# Schematic.net
KiCad netlist of a schematic drawn in Altium Designer
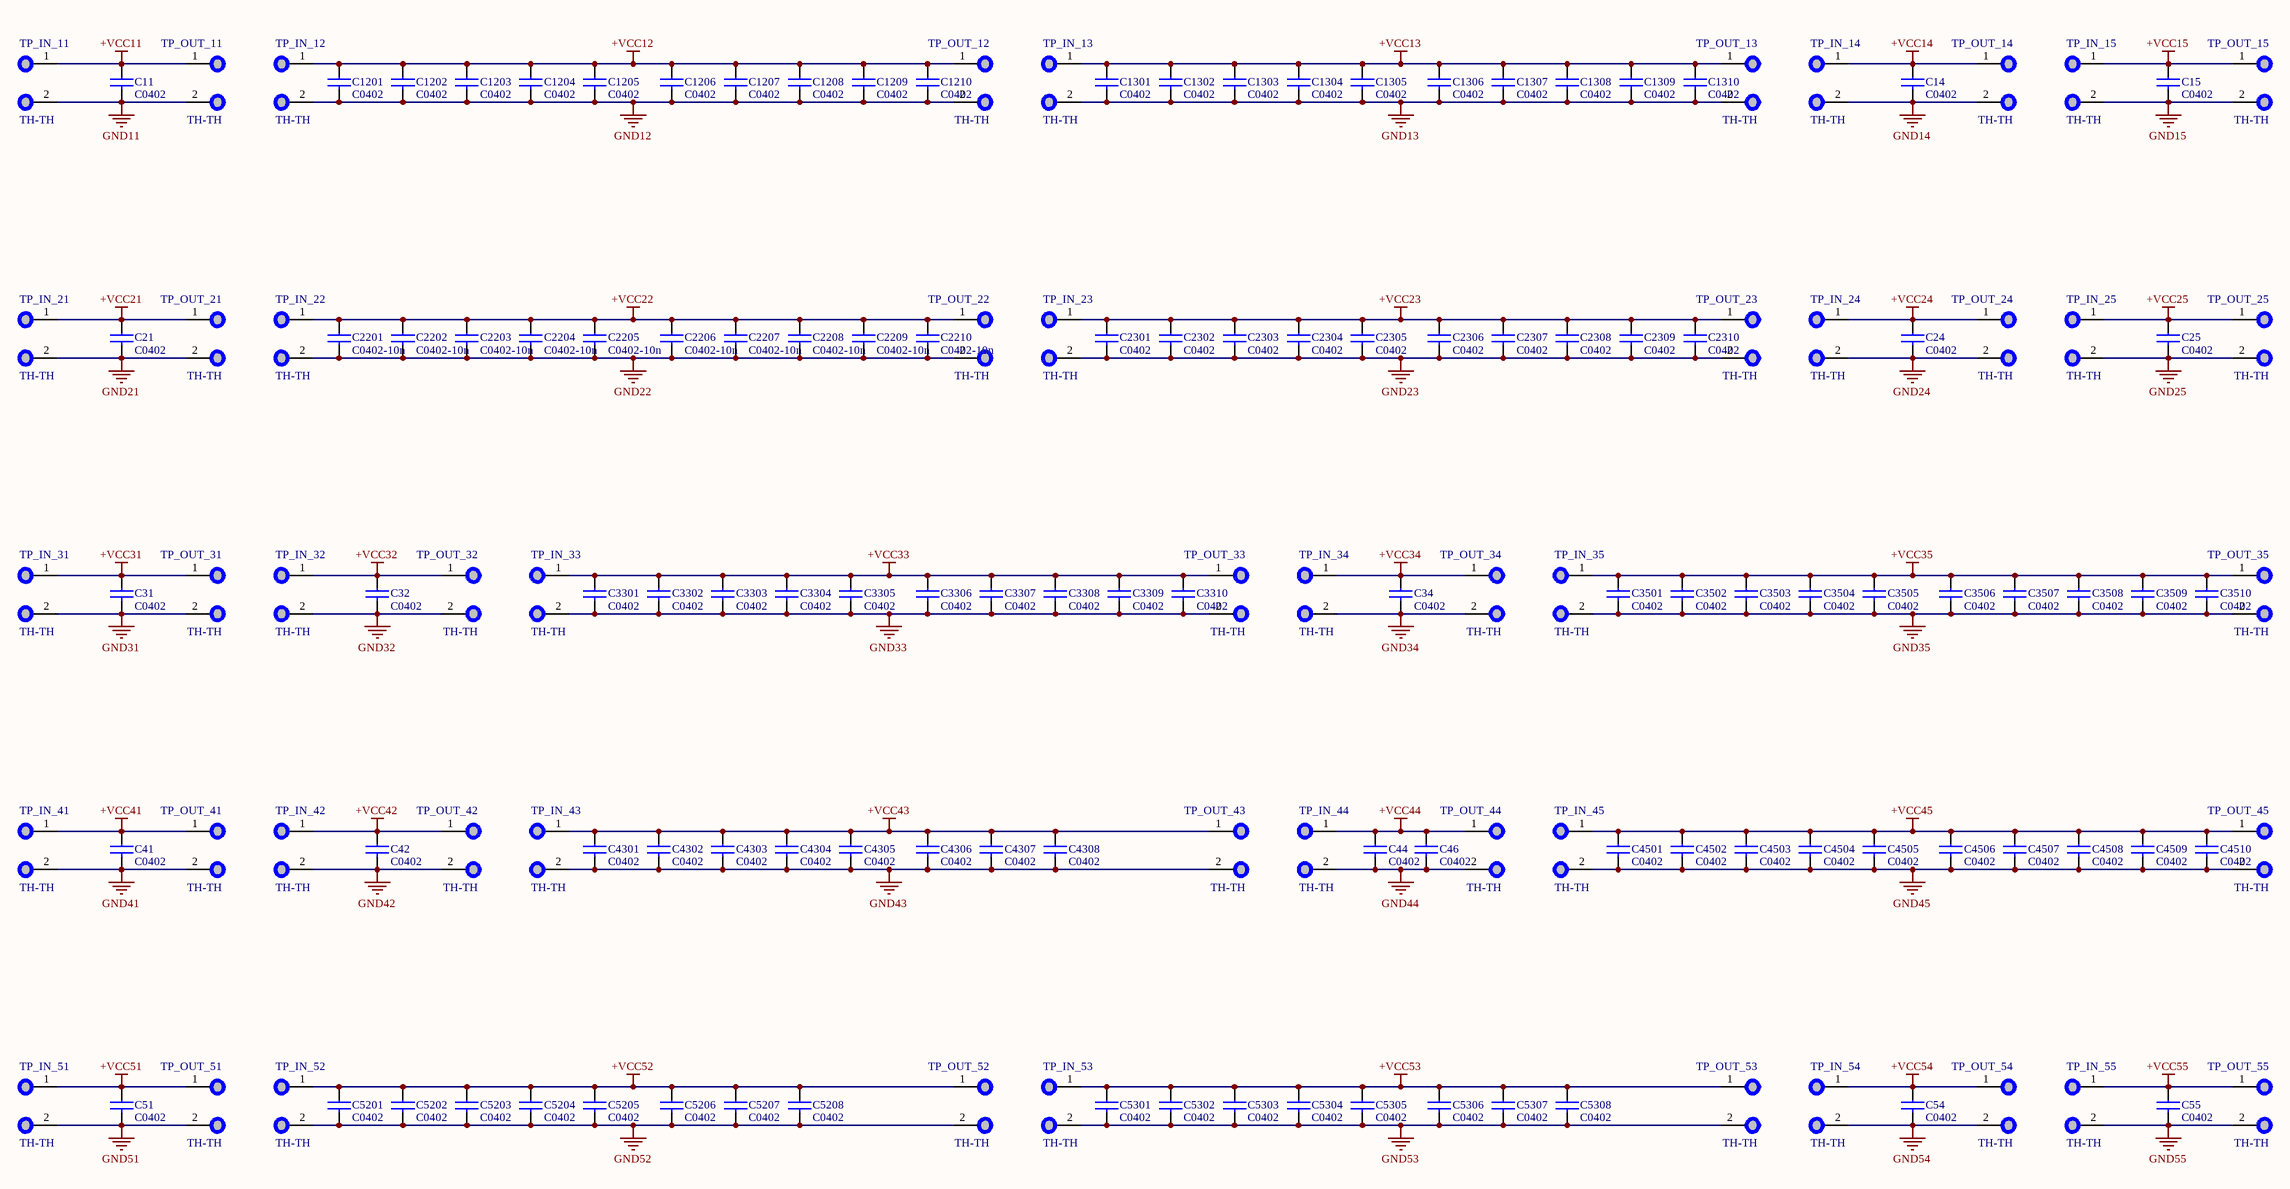
[diagram p0: Schematic.SchDoc]

(export (version "E")
  (design (tool "Eeschema 10.0.6"))
  (components
    (comp (ref "C11") (value "C0402") (footprint "C0402") (libsource (lib "Schlib") (part "CAP0402")))
    (comp (ref "C14") (value "C0402") (footprint "C0402") (libsource (lib "Schlib") (part "CAP0402")))
    (comp (ref "C15") (value "C0402") (footprint "C0402") (libsource (lib "Schlib") (part "CAP0402")))
    (comp (ref "C21") (value "C0402") (footprint "C0402") (libsource (lib "Schlib") (part "CAP0402")))
    (comp (ref "C24") (value "C0402") (footprint "C0402") (libsource (lib "Schlib") (part "CAP0402")))
    (comp (ref "C25") (value "C0402") (footprint "C0402") (libsource (lib "Schlib") (part "CAP0402")))
    (comp (ref "C31") (value "C0402") (footprint "C0402") (libsource (lib "Schlib") (part "CAP0402")))
    (comp (ref "C32") (value "C0402") (footprint "C0402") (libsource (lib "Schlib") (part "CAP0402")))
    (comp (ref "C34") (value "C0402") (footprint "C0402") (libsource (lib "Schlib") (part "CAP0402")))
    (comp (ref "C41") (value "C0402") (footprint "C0402") (libsource (lib "Schlib") (part "CAP0402")))
    (comp (ref "C42") (value "C0402") (footprint "C0402") (libsource (lib "Schlib") (part "CAP0402")))
    (comp (ref "C44") (value "C0402") (footprint "C0402") (libsource (lib "Schlib") (part "CAP0402")))
    (comp (ref "C46") (value "C0402") (footprint "C0402") (libsource (lib "Schlib") (part "CAP0402")))
    (comp (ref "C51") (value "C0402") (footprint "C0402") (libsource (lib "Schlib") (part "CAP0402")))
    (comp (ref "C54") (value "C0402") (footprint "C0402") (libsource (lib "Schlib") (part "CAP0402")))
    (comp (ref "C55") (value "C0402") (footprint "C0402") (libsource (lib "Schlib") (part "CAP0402")))
    (comp (ref "C1201") (value "C0402") (footprint "C0402") (libsource (lib "Schlib") (part "CAP0402")))
    (comp (ref "C1202") (value "C0402") (footprint "C0402") (libsource (lib "Schlib") (part "CAP0402")))
    (comp (ref "C1203") (value "C0402") (footprint "C0402") (libsource (lib "Schlib") (part "CAP0402")))
    (comp (ref "C1204") (value "C0402") (footprint "C0402") (libsource (lib "Schlib") (part "CAP0402")))
    (comp (ref "C1205") (value "C0402") (footprint "C0402") (libsource (lib "Schlib") (part "CAP0402")))
    (comp (ref "C1206") (value "C0402") (footprint "C0402") (libsource (lib "Schlib") (part "CAP0402")))
    (comp (ref "C1207") (value "C0402") (footprint "C0402") (libsource (lib "Schlib") (part "CAP0402")))
    (comp (ref "C1208") (value "C0402") (footprint "C0402") (libsource (lib "Schlib") (part "CAP0402")))
    (comp (ref "C1209") (value "C0402") (footprint "C0402") (libsource (lib "Schlib") (part "CAP0402")))
    (comp (ref "C1210") (value "C0402") (footprint "C0402") (libsource (lib "Schlib") (part "CAP0402")))
    (comp (ref "C1301") (value "C0402") (footprint "C0402") (libsource (lib "Schlib") (part "CAP0402")))
    (comp (ref "C1302") (value "C0402") (footprint "C0402") (libsource (lib "Schlib") (part "CAP0402")))
    (comp (ref "C1303") (value "C0402") (footprint "C0402") (libsource (lib "Schlib") (part "CAP0402")))
    (comp (ref "C1304") (value "C0402") (footprint "C0402") (libsource (lib "Schlib") (part "CAP0402")))
    (comp (ref "C1305") (value "C0402") (footprint "C0402") (libsource (lib "Schlib") (part "CAP0402")))
    (comp (ref "C1306") (value "C0402") (footprint "C0402") (libsource (lib "Schlib") (part "CAP0402")))
    (comp (ref "C1307") (value "C0402") (footprint "C0402") (libsource (lib "Schlib") (part "CAP0402")))
    (comp (ref "C1308") (value "C0402") (footprint "C0402") (libsource (lib "Schlib") (part "CAP0402")))
    (comp (ref "C1309") (value "C0402") (footprint "C0402") (libsource (lib "Schlib") (part "CAP0402")))
    (comp (ref "C1310") (value "C0402") (footprint "C0402") (libsource (lib "Schlib") (part "CAP0402")))
    (comp (ref "C2201") (value "C0402-10n") (footprint "C0402") (libsource (lib "Schlib") (part "CAP0402")))
    (comp (ref "C2202") (value "C0402-10n") (footprint "C0402") (libsource (lib "Schlib") (part "CAP0402")))
    (comp (ref "C2203") (value "C0402-10n") (footprint "C0402") (libsource (lib "Schlib") (part "CAP0402")))
    (comp (ref "C2204") (value "C0402-10n") (footprint "C0402") (libsource (lib "Schlib") (part "CAP0402")))
    (comp (ref "C2205") (value "C0402-10n") (footprint "C0402") (libsource (lib "Schlib") (part "CAP0402")))
    (comp (ref "C2206") (value "C0402-10n") (footprint "C0402") (libsource (lib "Schlib") (part "CAP0402")))
    (comp (ref "C2207") (value "C0402-10n") (footprint "C0402") (libsource (lib "Schlib") (part "CAP0402")))
    (comp (ref "C2208") (value "C0402-10n") (footprint "C0402") (libsource (lib "Schlib") (part "CAP0402")))
    (comp (ref "C2209") (value "C0402-10n") (footprint "C0402") (libsource (lib "Schlib") (part "CAP0402")))
    (comp (ref "C2210") (value "C0402-10n") (footprint "C0402") (libsource (lib "Schlib") (part "CAP0402")))
    (comp (ref "C2301") (value "C0402") (footprint "C0402") (libsource (lib "Schlib") (part "CAP0402")))
    (comp (ref "C2302") (value "C0402") (footprint "C0402") (libsource (lib "Schlib") (part "CAP0402")))
    (comp (ref "C2303") (value "C0402") (footprint "C0402") (libsource (lib "Schlib") (part "CAP0402")))
    (comp (ref "C2304") (value "C0402") (footprint "C0402") (libsource (lib "Schlib") (part "CAP0402")))
    (comp (ref "C2305") (value "C0402") (footprint "C0402") (libsource (lib "Schlib") (part "CAP0402")))
    (comp (ref "C2306") (value "C0402") (footprint "C0402") (libsource (lib "Schlib") (part "CAP0402")))
    (comp (ref "C2307") (value "C0402") (footprint "C0402") (libsource (lib "Schlib") (part "CAP0402")))
    (comp (ref "C2308") (value "C0402") (footprint "C0402") (libsource (lib "Schlib") (part "CAP0402")))
    (comp (ref "C2309") (value "C0402") (footprint "C0402") (libsource (lib "Schlib") (part "CAP0402")))
    (comp (ref "C2310") (value "C0402") (footprint "C0402") (libsource (lib "Schlib") (part "CAP0402")))
    (comp (ref "C3301") (value "C0402") (footprint "C0402") (libsource (lib "Schlib") (part "CAP0402")))
    (comp (ref "C3302") (value "C0402") (footprint "C0402") (libsource (lib "Schlib") (part "CAP0402")))
    (comp (ref "C3303") (value "C0402") (footprint "C0402") (libsource (lib "Schlib") (part "CAP0402")))
    (comp (ref "C3304") (value "C0402") (footprint "C0402") (libsource (lib "Schlib") (part "CAP0402")))
    (comp (ref "C3305") (value "C0402") (footprint "C0402") (libsource (lib "Schlib") (part "CAP0402")))
    (comp (ref "C3306") (value "C0402") (footprint "C0402") (libsource (lib "Schlib") (part "CAP0402")))
    (comp (ref "C3307") (value "C0402") (footprint "C0402") (libsource (lib "Schlib") (part "CAP0402")))
    (comp (ref "C3308") (value "C0402") (footprint "C0402") (libsource (lib "Schlib") (part "CAP0402")))
    (comp (ref "C3309") (value "C0402") (footprint "C0402") (libsource (lib "Schlib") (part "CAP0402")))
    (comp (ref "C3310") (value "C0402") (footprint "C0402") (libsource (lib "Schlib") (part "CAP0402")))
    (comp (ref "C3501") (value "C0402") (footprint "C0402") (libsource (lib "Schlib") (part "CAP0402")))
    (comp (ref "C3502") (value "C0402") (footprint "C0402") (libsource (lib "Schlib") (part "CAP0402")))
    (comp (ref "C3503") (value "C0402") (footprint "C0402") (libsource (lib "Schlib") (part "CAP0402")))
    (comp (ref "C3504") (value "C0402") (footprint "C0402") (libsource (lib "Schlib") (part "CAP0402")))
    (comp (ref "C3505") (value "C0402") (footprint "C0402") (libsource (lib "Schlib") (part "CAP0402")))
    (comp (ref "C3506") (value "C0402") (footprint "C0402") (libsource (lib "Schlib") (part "CAP0402")))
    (comp (ref "C3507") (value "C0402") (footprint "C0402") (libsource (lib "Schlib") (part "CAP0402")))
    (comp (ref "C3508") (value "C0402") (footprint "C0402") (libsource (lib "Schlib") (part "CAP0402")))
    (comp (ref "C3509") (value "C0402") (footprint "C0402") (libsource (lib "Schlib") (part "CAP0402")))
    (comp (ref "C3510") (value "C0402") (footprint "C0402") (libsource (lib "Schlib") (part "CAP0402")))
    (comp (ref "C4301") (value "C0402") (footprint "C0402") (libsource (lib "Schlib") (part "CAP0402")))
    (comp (ref "C4302") (value "C0402") (footprint "C0402") (libsource (lib "Schlib") (part "CAP0402")))
    (comp (ref "C4303") (value "C0402") (footprint "C0402") (libsource (lib "Schlib") (part "CAP0402")))
    (comp (ref "C4304") (value "C0402") (footprint "C0402") (libsource (lib "Schlib") (part "CAP0402")))
    (comp (ref "C4305") (value "C0402") (footprint "C0402") (libsource (lib "Schlib") (part "CAP0402")))
    (comp (ref "C4306") (value "C0402") (footprint "C0402") (libsource (lib "Schlib") (part "CAP0402")))
    (comp (ref "C4307") (value "C0402") (footprint "C0402") (libsource (lib "Schlib") (part "CAP0402")))
    (comp (ref "C4308") (value "C0402") (footprint "C0402") (libsource (lib "Schlib") (part "CAP0402")))
    (comp (ref "C4501") (value "C0402") (footprint "C0402") (libsource (lib "Schlib") (part "CAP0402")))
    (comp (ref "C4502") (value "C0402") (footprint "C0402") (libsource (lib "Schlib") (part "CAP0402")))
    (comp (ref "C4503") (value "C0402") (footprint "C0402") (libsource (lib "Schlib") (part "CAP0402")))
    (comp (ref "C4504") (value "C0402") (footprint "C0402") (libsource (lib "Schlib") (part "CAP0402")))
    (comp (ref "C4505") (value "C0402") (footprint "C0402") (libsource (lib "Schlib") (part "CAP0402")))
    (comp (ref "C4506") (value "C0402") (footprint "C0402") (libsource (lib "Schlib") (part "CAP0402")))
    (comp (ref "C4507") (value "C0402") (footprint "C0402") (libsource (lib "Schlib") (part "CAP0402")))
    (comp (ref "C4508") (value "C0402") (footprint "C0402") (libsource (lib "Schlib") (part "CAP0402")))
    (comp (ref "C4509") (value "C0402") (footprint "C0402") (libsource (lib "Schlib") (part "CAP0402")))
    (comp (ref "C4510") (value "C0402") (footprint "C0402") (libsource (lib "Schlib") (part "CAP0402")))
    (comp (ref "C5201") (value "C0402") (footprint "C0402") (libsource (lib "Schlib") (part "CAP0402")))
    (comp (ref "C5202") (value "C0402") (footprint "C0402") (libsource (lib "Schlib") (part "CAP0402")))
    (comp (ref "C5203") (value "C0402") (footprint "C0402") (libsource (lib "Schlib") (part "CAP0402")))
    (comp (ref "C5204") (value "C0402") (footprint "C0402") (libsource (lib "Schlib") (part "CAP0402")))
    (comp (ref "C5205") (value "C0402") (footprint "C0402") (libsource (lib "Schlib") (part "CAP0402")))
    (comp (ref "C5206") (value "C0402") (footprint "C0402") (libsource (lib "Schlib") (part "CAP0402")))
    (comp (ref "C5207") (value "C0402") (footprint "C0402") (libsource (lib "Schlib") (part "CAP0402")))
    (comp (ref "C5208") (value "C0402") (footprint "C0402") (libsource (lib "Schlib") (part "CAP0402")))
    (comp (ref "C5301") (value "C0402") (footprint "C0402") (libsource (lib "Schlib") (part "CAP0402")))
    (comp (ref "C5302") (value "C0402") (footprint "C0402") (libsource (lib "Schlib") (part "CAP0402")))
    (comp (ref "C5303") (value "C0402") (footprint "C0402") (libsource (lib "Schlib") (part "CAP0402")))
    (comp (ref "C5304") (value "C0402") (footprint "C0402") (libsource (lib "Schlib") (part "CAP0402")))
    (comp (ref "C5305") (value "C0402") (footprint "C0402") (libsource (lib "Schlib") (part "CAP0402")))
    (comp (ref "C5306") (value "C0402") (footprint "C0402") (libsource (lib "Schlib") (part "CAP0402")))
    (comp (ref "C5307") (value "C0402") (footprint "C0402") (libsource (lib "Schlib") (part "CAP0402")))
    (comp (ref "C5308") (value "C0402") (footprint "C0402") (libsource (lib "Schlib") (part "CAP0402")))
    (comp (ref "TP_IN_11")
      (value "TH-TH")
      (footprint "TP_TH_TH")
      (description "Testpoints TH - TH 1mm/0.3mm")
      (libsource (lib "Schlib") (part "TP_TH_TH"))
    )
    (comp (ref "TP_IN_12")
      (value "TH-TH")
      (footprint "TP_TH_TH")
      (description "Testpoints TH - TH 1mm/0.3mm")
      (libsource (lib "Schlib") (part "TP_TH_TH"))
    )
    (comp (ref "TP_IN_13")
      (value "TH-TH")
      (footprint "TP_TH_TH")
      (description "Testpoints TH - TH 1mm/0.3mm")
      (libsource (lib "Schlib") (part "TP_TH_TH"))
    )
    (comp (ref "TP_IN_14")
      (value "TH-TH")
      (footprint "TP_TH_TH")
      (description "Testpoints TH - TH 1mm/0.3mm")
      (libsource (lib "Schlib") (part "TP_TH_TH"))
    )
    (comp (ref "TP_IN_15")
      (value "TH-TH")
      (footprint "TP_TH_TH")
      (description "Testpoints TH - TH 1mm/0.3mm")
      (libsource (lib "Schlib") (part "TP_TH_TH"))
    )
    (comp (ref "TP_IN_21")
      (value "TH-TH")
      (footprint "TP_TH_TH")
      (description "Testpoints TH - TH 1mm/0.3mm")
      (libsource (lib "Schlib") (part "TP_TH_TH"))
    )
    (comp (ref "TP_IN_22")
      (value "TH-TH")
      (footprint "TP_TH_TH")
      (description "Testpoints TH - TH 1mm/0.3mm")
      (libsource (lib "Schlib") (part "TP_TH_TH"))
    )
    (comp (ref "TP_IN_23")
      (value "TH-TH")
      (footprint "TP_TH_TH")
      (description "Testpoints TH - TH 1mm/0.3mm")
      (libsource (lib "Schlib") (part "TP_TH_TH"))
    )
    (comp (ref "TP_IN_24")
      (value "TH-TH")
      (footprint "TP_TH_TH")
      (description "Testpoints TH - TH 1mm/0.3mm")
      (libsource (lib "Schlib") (part "TP_TH_TH"))
    )
    (comp (ref "TP_IN_25")
      (value "TH-TH")
      (footprint "TP_TH_TH")
      (description "Testpoints TH - TH 1mm/0.3mm")
      (libsource (lib "Schlib") (part "TP_TH_TH"))
    )
    (comp (ref "TP_IN_31")
      (value "TH-TH")
      (footprint "TP_TH_TH")
      (description "Testpoints TH - TH 1mm/0.3mm")
      (libsource (lib "Schlib") (part "TP_TH_TH"))
    )
    (comp (ref "TP_IN_32")
      (value "TH-TH")
      (footprint "TP_TH_TH")
      (description "Testpoints TH - TH 1mm/0.3mm")
      (libsource (lib "Schlib") (part "TP_TH_TH"))
    )
    (comp (ref "TP_IN_33")
      (value "TH-TH")
      (footprint "TP_TH_TH")
      (description "Testpoints TH - TH 1mm/0.3mm")
      (libsource (lib "Schlib") (part "TP_TH_TH"))
    )
    (comp (ref "TP_IN_34")
      (value "TH-TH")
      (footprint "TP_TH_TH")
      (description "Testpoints TH - TH 1mm/0.3mm")
      (libsource (lib "Schlib") (part "TP_TH_TH"))
    )
    (comp (ref "TP_IN_35")
      (value "TH-TH")
      (footprint "TP_TH_TH")
      (description "Testpoints TH - TH 1mm/0.3mm")
      (libsource (lib "Schlib") (part "TP_TH_TH"))
    )
    (comp (ref "TP_IN_41")
      (value "TH-TH")
      (footprint "TP_TH_TH")
      (description "Testpoints TH - TH 1mm/0.3mm")
      (libsource (lib "Schlib") (part "TP_TH_TH"))
    )
    (comp (ref "TP_IN_42")
      (value "TH-TH")
      (footprint "TP_TH_TH")
      (description "Testpoints TH - TH 1mm/0.3mm")
      (libsource (lib "Schlib") (part "TP_TH_TH"))
    )
    (comp (ref "TP_IN_43")
      (value "TH-TH")
      (footprint "TP_TH_TH")
      (description "Testpoints TH - TH 1mm/0.3mm")
      (libsource (lib "Schlib") (part "TP_TH_TH"))
    )
    (comp (ref "TP_IN_44")
      (value "TH-TH")
      (footprint "TP_TH_TH")
      (description "Testpoints TH - TH 1mm/0.3mm")
      (libsource (lib "Schlib") (part "TP_TH_TH"))
    )
    (comp (ref "TP_IN_45")
      (value "TH-TH")
      (footprint "TP_TH_TH")
      (description "Testpoints TH - TH 1mm/0.3mm")
      (libsource (lib "Schlib") (part "TP_TH_TH"))
    )
    (comp (ref "TP_IN_51")
      (value "TH-TH")
      (footprint "TP_TH_TH")
      (description "Testpoints TH - TH 1mm/0.3mm")
      (libsource (lib "Schlib") (part "TP_TH_TH"))
    )
    (comp (ref "TP_IN_52")
      (value "TH-TH")
      (footprint "TP_TH_TH")
      (description "Testpoints TH - TH 1mm/0.3mm")
      (libsource (lib "Schlib") (part "TP_TH_TH"))
    )
    (comp (ref "TP_IN_53")
      (value "TH-TH")
      (footprint "TP_TH_TH")
      (description "Testpoints TH - TH 1mm/0.3mm")
      (libsource (lib "Schlib") (part "TP_TH_TH"))
    )
    (comp (ref "TP_IN_54")
      (value "TH-TH")
      (footprint "TP_TH_TH")
      (description "Testpoints TH - TH 1mm/0.3mm")
      (libsource (lib "Schlib") (part "TP_TH_TH"))
    )
    (comp (ref "TP_IN_55")
      (value "TH-TH")
      (footprint "TP_TH_TH")
      (description "Testpoints TH - TH 1mm/0.3mm")
      (libsource (lib "Schlib") (part "TP_TH_TH"))
    )
    (comp (ref "TP_OUT_11")
      (value "TH-TH")
      (footprint "TP_TH_TH")
      (description "Testpoints TH - TH 1mm/0.3mm")
      (libsource (lib "Schlib") (part "TP_TH_TH"))
    )
    (comp (ref "TP_OUT_12")
      (value "TH-TH")
      (footprint "TP_TH_TH")
      (description "Testpoints TH - TH 1mm/0.3mm")
      (libsource (lib "Schlib") (part "TP_TH_TH"))
    )
    (comp (ref "TP_OUT_13")
      (value "TH-TH")
      (footprint "TP_TH_TH")
      (description "Testpoints TH - TH 1mm/0.3mm")
      (libsource (lib "Schlib") (part "TP_TH_TH"))
    )
    (comp (ref "TP_OUT_14")
      (value "TH-TH")
      (footprint "TP_TH_TH")
      (description "Testpoints TH - TH 1mm/0.3mm")
      (libsource (lib "Schlib") (part "TP_TH_TH"))
    )
    (comp (ref "TP_OUT_15")
      (value "TH-TH")
      (footprint "TP_TH_TH")
      (description "Testpoints TH - TH 1mm/0.3mm")
      (libsource (lib "Schlib") (part "TP_TH_TH"))
    )
    (comp (ref "TP_OUT_21")
      (value "TH-TH")
      (footprint "TP_TH_TH")
      (description "Testpoints TH - TH 1mm/0.3mm")
      (libsource (lib "Schlib") (part "TP_TH_TH"))
    )
    (comp (ref "TP_OUT_22")
      (value "TH-TH")
      (footprint "TP_TH_TH")
      (description "Testpoints TH - TH 1mm/0.3mm")
      (libsource (lib "Schlib") (part "TP_TH_TH"))
    )
    (comp (ref "TP_OUT_23")
      (value "TH-TH")
      (footprint "TP_TH_TH")
      (description "Testpoints TH - TH 1mm/0.3mm")
      (libsource (lib "Schlib") (part "TP_TH_TH"))
    )
    (comp (ref "TP_OUT_24")
      (value "TH-TH")
      (footprint "TP_TH_TH")
      (description "Testpoints TH - TH 1mm/0.3mm")
      (libsource (lib "Schlib") (part "TP_TH_TH"))
    )
    (comp (ref "TP_OUT_25")
      (value "TH-TH")
      (footprint "TP_TH_TH")
      (description "Testpoints TH - TH 1mm/0.3mm")
      (libsource (lib "Schlib") (part "TP_TH_TH"))
    )
    (comp (ref "TP_OUT_31")
      (value "TH-TH")
      (footprint "TP_TH_TH")
      (description "Testpoints TH - TH 1mm/0.3mm")
      (libsource (lib "Schlib") (part "TP_TH_TH"))
    )
    (comp (ref "TP_OUT_32")
      (value "TH-TH")
      (footprint "TP_TH_TH")
      (description "Testpoints TH - TH 1mm/0.3mm")
      (libsource (lib "Schlib") (part "TP_TH_TH"))
    )
    (comp (ref "TP_OUT_33")
      (value "TH-TH")
      (footprint "TP_TH_TH")
      (description "Testpoints TH - TH 1mm/0.3mm")
      (libsource (lib "Schlib") (part "TP_TH_TH"))
    )
    (comp (ref "TP_OUT_34")
      (value "TH-TH")
      (footprint "TP_TH_TH")
      (description "Testpoints TH - TH 1mm/0.3mm")
      (libsource (lib "Schlib") (part "TP_TH_TH"))
    )
    (comp (ref "TP_OUT_35")
      (value "TH-TH")
      (footprint "TP_TH_TH")
      (description "Testpoints TH - TH 1mm/0.3mm")
      (libsource (lib "Schlib") (part "TP_TH_TH"))
    )
    (comp (ref "TP_OUT_41")
      (value "TH-TH")
      (footprint "TP_TH_TH")
      (description "Testpoints TH - TH 1mm/0.3mm")
      (libsource (lib "Schlib") (part "TP_TH_TH"))
    )
    (comp (ref "TP_OUT_42")
      (value "TH-TH")
      (footprint "TP_TH_TH")
      (description "Testpoints TH - TH 1mm/0.3mm")
      (libsource (lib "Schlib") (part "TP_TH_TH"))
    )
    (comp (ref "TP_OUT_43")
      (value "TH-TH")
      (footprint "TP_TH_TH")
      (description "Testpoints TH - TH 1mm/0.3mm")
      (libsource (lib "Schlib") (part "TP_TH_TH"))
    )
    (comp (ref "TP_OUT_44")
      (value "TH-TH")
      (footprint "TP_TH_TH")
      (description "Testpoints TH - TH 1mm/0.3mm")
      (libsource (lib "Schlib") (part "TP_TH_TH"))
    )
    (comp (ref "TP_OUT_45")
      (value "TH-TH")
      (footprint "TP_TH_TH")
      (description "Testpoints TH - TH 1mm/0.3mm")
      (libsource (lib "Schlib") (part "TP_TH_TH"))
    )
    (comp (ref "TP_OUT_51")
      (value "TH-TH")
      (footprint "TP_TH_TH")
      (description "Testpoints TH - TH 1mm/0.3mm")
      (libsource (lib "Schlib") (part "TP_TH_TH"))
    )
    (comp (ref "TP_OUT_52")
      (value "TH-TH")
      (footprint "TP_TH_TH")
      (description "Testpoints TH - TH 1mm/0.3mm")
      (libsource (lib "Schlib") (part "TP_TH_TH"))
    )
    (comp (ref "TP_OUT_53")
      (value "TH-TH")
      (footprint "TP_TH_TH")
      (description "Testpoints TH - TH 1mm/0.3mm")
      (libsource (lib "Schlib") (part "TP_TH_TH"))
    )
    (comp (ref "TP_OUT_54")
      (value "TH-TH")
      (footprint "TP_TH_TH")
      (description "Testpoints TH - TH 1mm/0.3mm")
      (libsource (lib "Schlib") (part "TP_TH_TH"))
    )
    (comp (ref "TP_OUT_55")
      (value "TH-TH")
      (footprint "TP_TH_TH")
      (description "Testpoints TH - TH 1mm/0.3mm")
      (libsource (lib "Schlib") (part "TP_TH_TH"))
    )
  )
  (nets
    (net (code "1") (name "+VCC11") (class "Default")
      (node (ref "C11") (pin "1") (pinfunction "1_1") (pintype "passive"))
      (node (ref "TP_IN_11") (pin "1") (pinfunction "1_1") (pintype "passive"))
      (node (ref "TP_OUT_11") (pin "1") (pinfunction "1_1") (pintype "passive"))
    )
    (net (code "2") (name "+VCC12") (class "Default")
      (node (ref "C1201") (pin "1") (pinfunction "1_1") (pintype "passive"))
      (node (ref "C1202") (pin "1") (pinfunction "1_1") (pintype "passive"))
      (node (ref "C1203") (pin "1") (pinfunction "1_1") (pintype "passive"))
      (node (ref "C1204") (pin "1") (pinfunction "1_1") (pintype "passive"))
      (node (ref "C1205") (pin "1") (pinfunction "1_1") (pintype "passive"))
      (node (ref "C1206") (pin "1") (pinfunction "1_1") (pintype "passive"))
      (node (ref "C1207") (pin "1") (pinfunction "1_1") (pintype "passive"))
      (node (ref "C1208") (pin "1") (pinfunction "1_1") (pintype "passive"))
      (node (ref "C1209") (pin "1") (pinfunction "1_1") (pintype "passive"))
      (node (ref "C1210") (pin "1") (pinfunction "1_1") (pintype "passive"))
      (node (ref "TP_IN_12") (pin "1") (pinfunction "1_1") (pintype "passive"))
      (node (ref "TP_OUT_12") (pin "1") (pinfunction "1_1") (pintype "passive"))
    )
    (net (code "3") (name "+VCC13") (class "Default")
      (node (ref "C1301") (pin "1") (pinfunction "1_1") (pintype "passive"))
      (node (ref "C1302") (pin "1") (pinfunction "1_1") (pintype "passive"))
      (node (ref "C1303") (pin "1") (pinfunction "1_1") (pintype "passive"))
      (node (ref "C1304") (pin "1") (pinfunction "1_1") (pintype "passive"))
      (node (ref "C1305") (pin "1") (pinfunction "1_1") (pintype "passive"))
      (node (ref "C1306") (pin "1") (pinfunction "1_1") (pintype "passive"))
      (node (ref "C1307") (pin "1") (pinfunction "1_1") (pintype "passive"))
      (node (ref "C1308") (pin "1") (pinfunction "1_1") (pintype "passive"))
      (node (ref "C1309") (pin "1") (pinfunction "1_1") (pintype "passive"))
      (node (ref "C1310") (pin "1") (pinfunction "1_1") (pintype "passive"))
      (node (ref "TP_IN_13") (pin "1") (pinfunction "1_1") (pintype "passive"))
      (node (ref "TP_OUT_13") (pin "1") (pinfunction "1_1") (pintype "passive"))
    )
    (net (code "4") (name "+VCC14") (class "Default")
      (node (ref "C14") (pin "1") (pinfunction "1_1") (pintype "passive"))
      (node (ref "TP_IN_14") (pin "1") (pinfunction "1_1") (pintype "passive"))
      (node (ref "TP_OUT_14") (pin "1") (pinfunction "1_1") (pintype "passive"))
    )
    (net (code "5") (name "+VCC15") (class "Default")
      (node (ref "C15") (pin "1") (pinfunction "1_1") (pintype "passive"))
      (node (ref "TP_IN_15") (pin "1") (pinfunction "1_1") (pintype "passive"))
      (node (ref "TP_OUT_15") (pin "1") (pinfunction "1_1") (pintype "passive"))
    )
    (net (code "6") (name "+VCC21") (class "Default")
      (node (ref "C21") (pin "1") (pinfunction "1_1") (pintype "passive"))
      (node (ref "TP_IN_21") (pin "1") (pinfunction "1_1") (pintype "passive"))
      (node (ref "TP_OUT_21") (pin "1") (pinfunction "1_1") (pintype "passive"))
    )
    (net (code "7") (name "+VCC22") (class "Default")
      (node (ref "C2201") (pin "1") (pinfunction "1_1") (pintype "passive"))
      (node (ref "C2202") (pin "1") (pinfunction "1_1") (pintype "passive"))
      (node (ref "C2203") (pin "1") (pinfunction "1_1") (pintype "passive"))
      (node (ref "C2204") (pin "1") (pinfunction "1_1") (pintype "passive"))
      (node (ref "C2205") (pin "1") (pinfunction "1_1") (pintype "passive"))
      (node (ref "C2206") (pin "1") (pinfunction "1_1") (pintype "passive"))
      (node (ref "C2207") (pin "1") (pinfunction "1_1") (pintype "passive"))
      (node (ref "C2208") (pin "1") (pinfunction "1_1") (pintype "passive"))
      (node (ref "C2209") (pin "1") (pinfunction "1_1") (pintype "passive"))
      (node (ref "C2210") (pin "1") (pinfunction "1_1") (pintype "passive"))
      (node (ref "TP_IN_22") (pin "1") (pinfunction "1_1") (pintype "passive"))
      (node (ref "TP_OUT_22") (pin "1") (pinfunction "1_1") (pintype "passive"))
    )
    (net (code "8") (name "+VCC23") (class "Default")
      (node (ref "C2301") (pin "1") (pinfunction "1_1") (pintype "passive"))
      (node (ref "C2302") (pin "1") (pinfunction "1_1") (pintype "passive"))
      (node (ref "C2303") (pin "1") (pinfunction "1_1") (pintype "passive"))
      (node (ref "C2304") (pin "1") (pinfunction "1_1") (pintype "passive"))
      (node (ref "C2305") (pin "1") (pinfunction "1_1") (pintype "passive"))
      (node (ref "C2306") (pin "1") (pinfunction "1_1") (pintype "passive"))
      (node (ref "C2307") (pin "1") (pinfunction "1_1") (pintype "passive"))
      (node (ref "C2308") (pin "1") (pinfunction "1_1") (pintype "passive"))
      (node (ref "C2309") (pin "1") (pinfunction "1_1") (pintype "passive"))
      (node (ref "C2310") (pin "1") (pinfunction "1_1") (pintype "passive"))
      (node (ref "TP_IN_23") (pin "1") (pinfunction "1_1") (pintype "passive"))
      (node (ref "TP_OUT_23") (pin "1") (pinfunction "1_1") (pintype "passive"))
    )
    (net (code "9") (name "+VCC24") (class "Default")
      (node (ref "C24") (pin "1") (pinfunction "1_1") (pintype "passive"))
      (node (ref "TP_IN_24") (pin "1") (pinfunction "1_1") (pintype "passive"))
      (node (ref "TP_OUT_24") (pin "1") (pinfunction "1_1") (pintype "passive"))
    )
    (net (code "10") (name "+VCC25") (class "Default")
      (node (ref "C25") (pin "1") (pinfunction "1_1") (pintype "passive"))
      (node (ref "TP_IN_25") (pin "1") (pinfunction "1_1") (pintype "passive"))
      (node (ref "TP_OUT_25") (pin "1") (pinfunction "1_1") (pintype "passive"))
    )
    (net (code "11") (name "+VCC31") (class "Default")
      (node (ref "C31") (pin "1") (pinfunction "1_1") (pintype "passive"))
      (node (ref "TP_IN_31") (pin "1") (pinfunction "1_1") (pintype "passive"))
      (node (ref "TP_OUT_31") (pin "1") (pinfunction "1_1") (pintype "passive"))
    )
    (net (code "12") (name "+VCC32") (class "Default")
      (node (ref "C32") (pin "1") (pinfunction "1_1") (pintype "passive"))
      (node (ref "TP_IN_32") (pin "1") (pinfunction "1_1") (pintype "passive"))
      (node (ref "TP_OUT_32") (pin "1") (pinfunction "1_1") (pintype "passive"))
    )
    (net (code "13") (name "+VCC33") (class "Default")
      (node (ref "C3301") (pin "1") (pinfunction "1_1") (pintype "passive"))
      (node (ref "C3302") (pin "1") (pinfunction "1_1") (pintype "passive"))
      (node (ref "C3303") (pin "1") (pinfunction "1_1") (pintype "passive"))
      (node (ref "C3304") (pin "1") (pinfunction "1_1") (pintype "passive"))
      (node (ref "C3305") (pin "1") (pinfunction "1_1") (pintype "passive"))
      (node (ref "C3306") (pin "1") (pinfunction "1_1") (pintype "passive"))
      (node (ref "C3307") (pin "1") (pinfunction "1_1") (pintype "passive"))
      (node (ref "C3308") (pin "1") (pinfunction "1_1") (pintype "passive"))
      (node (ref "C3309") (pin "1") (pinfunction "1_1") (pintype "passive"))
      (node (ref "C3310") (pin "1") (pinfunction "1_1") (pintype "passive"))
      (node (ref "TP_IN_33") (pin "1") (pinfunction "1_1") (pintype "passive"))
      (node (ref "TP_OUT_33") (pin "1") (pinfunction "1_1") (pintype "passive"))
    )
    (net (code "14") (name "+VCC34") (class "Default")
      (node (ref "C34") (pin "1") (pinfunction "1_1") (pintype "passive"))
      (node (ref "TP_IN_34") (pin "1") (pinfunction "1_1") (pintype "passive"))
      (node (ref "TP_OUT_34") (pin "1") (pinfunction "1_1") (pintype "passive"))
    )
    (net (code "15") (name "+VCC35") (class "Default")
      (node (ref "C3501") (pin "1") (pinfunction "1_1") (pintype "passive"))
      (node (ref "C3502") (pin "1") (pinfunction "1_1") (pintype "passive"))
      (node (ref "C3503") (pin "1") (pinfunction "1_1") (pintype "passive"))
      (node (ref "C3504") (pin "1") (pinfunction "1_1") (pintype "passive"))
      (node (ref "C3505") (pin "1") (pinfunction "1_1") (pintype "passive"))
      (node (ref "C3506") (pin "1") (pinfunction "1_1") (pintype "passive"))
      (node (ref "C3507") (pin "1") (pinfunction "1_1") (pintype "passive"))
      (node (ref "C3508") (pin "1") (pinfunction "1_1") (pintype "passive"))
      (node (ref "C3509") (pin "1") (pinfunction "1_1") (pintype "passive"))
      (node (ref "C3510") (pin "1") (pinfunction "1_1") (pintype "passive"))
      (node (ref "TP_IN_35") (pin "1") (pinfunction "1_1") (pintype "passive"))
      (node (ref "TP_OUT_35") (pin "1") (pinfunction "1_1") (pintype "passive"))
    )
    (net (code "16") (name "+VCC41") (class "Default")
      (node (ref "C41") (pin "1") (pinfunction "1_1") (pintype "passive"))
      (node (ref "TP_IN_41") (pin "1") (pinfunction "1_1") (pintype "passive"))
      (node (ref "TP_OUT_41") (pin "1") (pinfunction "1_1") (pintype "passive"))
    )
    (net (code "17") (name "+VCC42") (class "Default")
      (node (ref "C42") (pin "1") (pinfunction "1_1") (pintype "passive"))
      (node (ref "TP_IN_42") (pin "1") (pinfunction "1_1") (pintype "passive"))
      (node (ref "TP_OUT_42") (pin "1") (pinfunction "1_1") (pintype "passive"))
    )
    (net (code "18") (name "+VCC43") (class "Default")
      (node (ref "C4301") (pin "1") (pinfunction "1_1") (pintype "passive"))
      (node (ref "C4302") (pin "1") (pinfunction "1_1") (pintype "passive"))
      (node (ref "C4303") (pin "1") (pinfunction "1_1") (pintype "passive"))
      (node (ref "C4304") (pin "1") (pinfunction "1_1") (pintype "passive"))
      (node (ref "C4305") (pin "1") (pinfunction "1_1") (pintype "passive"))
      (node (ref "C4306") (pin "1") (pinfunction "1_1") (pintype "passive"))
      (node (ref "C4307") (pin "1") (pinfunction "1_1") (pintype "passive"))
      (node (ref "C4308") (pin "1") (pinfunction "1_1") (pintype "passive"))
      (node (ref "TP_IN_43") (pin "1") (pinfunction "1_1") (pintype "passive"))
      (node (ref "TP_OUT_43") (pin "1") (pinfunction "1_1") (pintype "passive"))
    )
    (net (code "19") (name "+VCC44") (class "Default")
      (node (ref "C44") (pin "1") (pinfunction "1_1") (pintype "passive"))
      (node (ref "C46") (pin "1") (pinfunction "1_1") (pintype "passive"))
      (node (ref "TP_IN_44") (pin "1") (pinfunction "1_1") (pintype "passive"))
      (node (ref "TP_OUT_44") (pin "1") (pinfunction "1_1") (pintype "passive"))
    )
    (net (code "20") (name "+VCC45") (class "Default")
      (node (ref "C4501") (pin "1") (pinfunction "1_1") (pintype "passive"))
      (node (ref "C4502") (pin "1") (pinfunction "1_1") (pintype "passive"))
      (node (ref "C4503") (pin "1") (pinfunction "1_1") (pintype "passive"))
      (node (ref "C4504") (pin "1") (pinfunction "1_1") (pintype "passive"))
      (node (ref "C4505") (pin "1") (pinfunction "1_1") (pintype "passive"))
      (node (ref "C4506") (pin "1") (pinfunction "1_1") (pintype "passive"))
      (node (ref "C4507") (pin "1") (pinfunction "1_1") (pintype "passive"))
      (node (ref "C4508") (pin "1") (pinfunction "1_1") (pintype "passive"))
      (node (ref "C4509") (pin "1") (pinfunction "1_1") (pintype "passive"))
      (node (ref "C4510") (pin "1") (pinfunction "1_1") (pintype "passive"))
      (node (ref "TP_IN_45") (pin "1") (pinfunction "1_1") (pintype "passive"))
      (node (ref "TP_OUT_45") (pin "1") (pinfunction "1_1") (pintype "passive"))
    )
    (net (code "21") (name "+VCC51") (class "Default")
      (node (ref "C51") (pin "1") (pinfunction "1_1") (pintype "passive"))
      (node (ref "TP_IN_51") (pin "1") (pinfunction "1_1") (pintype "passive"))
      (node (ref "TP_OUT_51") (pin "1") (pinfunction "1_1") (pintype "passive"))
    )
    (net (code "22") (name "+VCC52") (class "Default")
      (node (ref "C5201") (pin "1") (pinfunction "1_1") (pintype "passive"))
      (node (ref "C5202") (pin "1") (pinfunction "1_1") (pintype "passive"))
      (node (ref "C5203") (pin "1") (pinfunction "1_1") (pintype "passive"))
      (node (ref "C5204") (pin "1") (pinfunction "1_1") (pintype "passive"))
      (node (ref "C5205") (pin "1") (pinfunction "1_1") (pintype "passive"))
      (node (ref "C5206") (pin "1") (pinfunction "1_1") (pintype "passive"))
      (node (ref "C5207") (pin "1") (pinfunction "1_1") (pintype "passive"))
      (node (ref "C5208") (pin "1") (pinfunction "1_1") (pintype "passive"))
      (node (ref "TP_IN_52") (pin "1") (pinfunction "1_1") (pintype "passive"))
      (node (ref "TP_OUT_52") (pin "1") (pinfunction "1_1") (pintype "passive"))
    )
    (net (code "23") (name "+VCC53") (class "Default")
      (node (ref "C5301") (pin "1") (pinfunction "1_1") (pintype "passive"))
      (node (ref "C5302") (pin "1") (pinfunction "1_1") (pintype "passive"))
      (node (ref "C5303") (pin "1") (pinfunction "1_1") (pintype "passive"))
      (node (ref "C5304") (pin "1") (pinfunction "1_1") (pintype "passive"))
      (node (ref "C5305") (pin "1") (pinfunction "1_1") (pintype "passive"))
      (node (ref "C5306") (pin "1") (pinfunction "1_1") (pintype "passive"))
      (node (ref "C5307") (pin "1") (pinfunction "1_1") (pintype "passive"))
      (node (ref "C5308") (pin "1") (pinfunction "1_1") (pintype "passive"))
      (node (ref "TP_IN_53") (pin "1") (pinfunction "1_1") (pintype "passive"))
      (node (ref "TP_OUT_53") (pin "1") (pinfunction "1_1") (pintype "passive"))
    )
    (net (code "24") (name "+VCC54") (class "Default")
      (node (ref "C54") (pin "1") (pinfunction "1_1") (pintype "passive"))
      (node (ref "TP_IN_54") (pin "1") (pinfunction "1_1") (pintype "passive"))
      (node (ref "TP_OUT_54") (pin "1") (pinfunction "1_1") (pintype "passive"))
    )
    (net (code "25") (name "+VCC55") (class "Default")
      (node (ref "C55") (pin "1") (pinfunction "1_1") (pintype "passive"))
      (node (ref "TP_IN_55") (pin "1") (pinfunction "1_1") (pintype "passive"))
      (node (ref "TP_OUT_55") (pin "1") (pinfunction "1_1") (pintype "passive"))
    )
    (net (code "26") (name "GND11") (class "Default")
      (node (ref "C11") (pin "2") (pinfunction "2_2") (pintype "passive"))
      (node (ref "TP_IN_11") (pin "2") (pinfunction "2_2") (pintype "passive"))
      (node (ref "TP_OUT_11") (pin "2") (pinfunction "2_2") (pintype "passive"))
    )
    (net (code "27") (name "GND12") (class "Default")
      (node (ref "C1201") (pin "2") (pinfunction "2_2") (pintype "passive"))
      (node (ref "C1202") (pin "2") (pinfunction "2_2") (pintype "passive"))
      (node (ref "C1203") (pin "2") (pinfunction "2_2") (pintype "passive"))
      (node (ref "C1204") (pin "2") (pinfunction "2_2") (pintype "passive"))
      (node (ref "C1205") (pin "2") (pinfunction "2_2") (pintype "passive"))
      (node (ref "C1206") (pin "2") (pinfunction "2_2") (pintype "passive"))
      (node (ref "C1207") (pin "2") (pinfunction "2_2") (pintype "passive"))
      (node (ref "C1208") (pin "2") (pinfunction "2_2") (pintype "passive"))
      (node (ref "C1209") (pin "2") (pinfunction "2_2") (pintype "passive"))
      (node (ref "C1210") (pin "2") (pinfunction "2_2") (pintype "passive"))
      (node (ref "TP_IN_12") (pin "2") (pinfunction "2_2") (pintype "passive"))
      (node (ref "TP_OUT_12") (pin "2") (pinfunction "2_2") (pintype "passive"))
    )
    (net (code "28") (name "GND13") (class "Default")
      (node (ref "C1301") (pin "2") (pinfunction "2_2") (pintype "passive"))
      (node (ref "C1302") (pin "2") (pinfunction "2_2") (pintype "passive"))
      (node (ref "C1303") (pin "2") (pinfunction "2_2") (pintype "passive"))
      (node (ref "C1304") (pin "2") (pinfunction "2_2") (pintype "passive"))
      (node (ref "C1305") (pin "2") (pinfunction "2_2") (pintype "passive"))
      (node (ref "C1306") (pin "2") (pinfunction "2_2") (pintype "passive"))
      (node (ref "C1307") (pin "2") (pinfunction "2_2") (pintype "passive"))
      (node (ref "C1308") (pin "2") (pinfunction "2_2") (pintype "passive"))
      (node (ref "C1309") (pin "2") (pinfunction "2_2") (pintype "passive"))
      (node (ref "C1310") (pin "2") (pinfunction "2_2") (pintype "passive"))
      (node (ref "TP_IN_13") (pin "2") (pinfunction "2_2") (pintype "passive"))
      (node (ref "TP_OUT_13") (pin "2") (pinfunction "2_2") (pintype "passive"))
    )
    (net (code "29") (name "GND14") (class "Default")
      (node (ref "C14") (pin "2") (pinfunction "2_2") (pintype "passive"))
      (node (ref "TP_IN_14") (pin "2") (pinfunction "2_2") (pintype "passive"))
      (node (ref "TP_OUT_14") (pin "2") (pinfunction "2_2") (pintype "passive"))
    )
    (net (code "30") (name "GND15") (class "Default")
      (node (ref "C15") (pin "2") (pinfunction "2_2") (pintype "passive"))
      (node (ref "TP_IN_15") (pin "2") (pinfunction "2_2") (pintype "passive"))
      (node (ref "TP_OUT_15") (pin "2") (pinfunction "2_2") (pintype "passive"))
    )
    (net (code "31") (name "GND21") (class "Default")
      (node (ref "C21") (pin "2") (pinfunction "2_2") (pintype "passive"))
      (node (ref "TP_IN_21") (pin "2") (pinfunction "2_2") (pintype "passive"))
      (node (ref "TP_OUT_21") (pin "2") (pinfunction "2_2") (pintype "passive"))
    )
    (net (code "32") (name "GND22") (class "Default")
      (node (ref "C2201") (pin "2") (pinfunction "2_2") (pintype "passive"))
      (node (ref "C2202") (pin "2") (pinfunction "2_2") (pintype "passive"))
      (node (ref "C2203") (pin "2") (pinfunction "2_2") (pintype "passive"))
      (node (ref "C2204") (pin "2") (pinfunction "2_2") (pintype "passive"))
      (node (ref "C2205") (pin "2") (pinfunction "2_2") (pintype "passive"))
      (node (ref "C2206") (pin "2") (pinfunction "2_2") (pintype "passive"))
      (node (ref "C2207") (pin "2") (pinfunction "2_2") (pintype "passive"))
      (node (ref "C2208") (pin "2") (pinfunction "2_2") (pintype "passive"))
      (node (ref "C2209") (pin "2") (pinfunction "2_2") (pintype "passive"))
      (node (ref "C2210") (pin "2") (pinfunction "2_2") (pintype "passive"))
      (node (ref "TP_IN_22") (pin "2") (pinfunction "2_2") (pintype "passive"))
      (node (ref "TP_OUT_22") (pin "2") (pinfunction "2_2") (pintype "passive"))
    )
    (net (code "33") (name "GND23") (class "Default")
      (node (ref "C2301") (pin "2") (pinfunction "2_2") (pintype "passive"))
      (node (ref "C2302") (pin "2") (pinfunction "2_2") (pintype "passive"))
      (node (ref "C2303") (pin "2") (pinfunction "2_2") (pintype "passive"))
      (node (ref "C2304") (pin "2") (pinfunction "2_2") (pintype "passive"))
      (node (ref "C2305") (pin "2") (pinfunction "2_2") (pintype "passive"))
      (node (ref "C2306") (pin "2") (pinfunction "2_2") (pintype "passive"))
      (node (ref "C2307") (pin "2") (pinfunction "2_2") (pintype "passive"))
      (node (ref "C2308") (pin "2") (pinfunction "2_2") (pintype "passive"))
      (node (ref "C2309") (pin "2") (pinfunction "2_2") (pintype "passive"))
      (node (ref "C2310") (pin "2") (pinfunction "2_2") (pintype "passive"))
      (node (ref "TP_IN_23") (pin "2") (pinfunction "2_2") (pintype "passive"))
      (node (ref "TP_OUT_23") (pin "2") (pinfunction "2_2") (pintype "passive"))
    )
    (net (code "34") (name "GND24") (class "Default")
      (node (ref "C24") (pin "2") (pinfunction "2_2") (pintype "passive"))
      (node (ref "TP_IN_24") (pin "2") (pinfunction "2_2") (pintype "passive"))
      (node (ref "TP_OUT_24") (pin "2") (pinfunction "2_2") (pintype "passive"))
    )
    (net (code "35") (name "GND25") (class "Default")
      (node (ref "C25") (pin "2") (pinfunction "2_2") (pintype "passive"))
      (node (ref "TP_IN_25") (pin "2") (pinfunction "2_2") (pintype "passive"))
      (node (ref "TP_OUT_25") (pin "2") (pinfunction "2_2") (pintype "passive"))
    )
    (net (code "36") (name "GND31") (class "Default")
      (node (ref "C31") (pin "2") (pinfunction "2_2") (pintype "passive"))
      (node (ref "TP_IN_31") (pin "2") (pinfunction "2_2") (pintype "passive"))
      (node (ref "TP_OUT_31") (pin "2") (pinfunction "2_2") (pintype "passive"))
    )
    (net (code "37") (name "GND32") (class "Default")
      (node (ref "C32") (pin "2") (pinfunction "2_2") (pintype "passive"))
      (node (ref "TP_IN_32") (pin "2") (pinfunction "2_2") (pintype "passive"))
      (node (ref "TP_OUT_32") (pin "2") (pinfunction "2_2") (pintype "passive"))
    )
    (net (code "38") (name "GND33") (class "Default")
      (node (ref "C3301") (pin "2") (pinfunction "2_2") (pintype "passive"))
      (node (ref "C3302") (pin "2") (pinfunction "2_2") (pintype "passive"))
      (node (ref "C3303") (pin "2") (pinfunction "2_2") (pintype "passive"))
      (node (ref "C3304") (pin "2") (pinfunction "2_2") (pintype "passive"))
      (node (ref "C3305") (pin "2") (pinfunction "2_2") (pintype "passive"))
      (node (ref "C3306") (pin "2") (pinfunction "2_2") (pintype "passive"))
      (node (ref "C3307") (pin "2") (pinfunction "2_2") (pintype "passive"))
      (node (ref "C3308") (pin "2") (pinfunction "2_2") (pintype "passive"))
      (node (ref "C3309") (pin "2") (pinfunction "2_2") (pintype "passive"))
      (node (ref "C3310") (pin "2") (pinfunction "2_2") (pintype "passive"))
      (node (ref "TP_IN_33") (pin "2") (pinfunction "2_2") (pintype "passive"))
      (node (ref "TP_OUT_33") (pin "2") (pinfunction "2_2") (pintype "passive"))
    )
    (net (code "39") (name "GND34") (class "Default")
      (node (ref "C34") (pin "2") (pinfunction "2_2") (pintype "passive"))
      (node (ref "TP_IN_34") (pin "2") (pinfunction "2_2") (pintype "passive"))
      (node (ref "TP_OUT_34") (pin "2") (pinfunction "2_2") (pintype "passive"))
    )
    (net (code "40") (name "GND35") (class "Default")
      (node (ref "C3501") (pin "2") (pinfunction "2_2") (pintype "passive"))
      (node (ref "C3502") (pin "2") (pinfunction "2_2") (pintype "passive"))
      (node (ref "C3503") (pin "2") (pinfunction "2_2") (pintype "passive"))
      (node (ref "C3504") (pin "2") (pinfunction "2_2") (pintype "passive"))
      (node (ref "C3505") (pin "2") (pinfunction "2_2") (pintype "passive"))
      (node (ref "C3506") (pin "2") (pinfunction "2_2") (pintype "passive"))
      (node (ref "C3507") (pin "2") (pinfunction "2_2") (pintype "passive"))
      (node (ref "C3508") (pin "2") (pinfunction "2_2") (pintype "passive"))
      (node (ref "C3509") (pin "2") (pinfunction "2_2") (pintype "passive"))
      (node (ref "C3510") (pin "2") (pinfunction "2_2") (pintype "passive"))
      (node (ref "TP_IN_35") (pin "2") (pinfunction "2_2") (pintype "passive"))
      (node (ref "TP_OUT_35") (pin "2") (pinfunction "2_2") (pintype "passive"))
    )
    (net (code "41") (name "GND41") (class "Default")
      (node (ref "C41") (pin "2") (pinfunction "2_2") (pintype "passive"))
      (node (ref "TP_IN_41") (pin "2") (pinfunction "2_2") (pintype "passive"))
      (node (ref "TP_OUT_41") (pin "2") (pinfunction "2_2") (pintype "passive"))
    )
    (net (code "42") (name "GND42") (class "Default")
      (node (ref "C42") (pin "2") (pinfunction "2_2") (pintype "passive"))
      (node (ref "TP_IN_42") (pin "2") (pinfunction "2_2") (pintype "passive"))
      (node (ref "TP_OUT_42") (pin "2") (pinfunction "2_2") (pintype "passive"))
    )
    (net (code "43") (name "GND43") (class "Default")
      (node (ref "C4301") (pin "2") (pinfunction "2_2") (pintype "passive"))
      (node (ref "C4302") (pin "2") (pinfunction "2_2") (pintype "passive"))
      (node (ref "C4303") (pin "2") (pinfunction "2_2") (pintype "passive"))
      (node (ref "C4304") (pin "2") (pinfunction "2_2") (pintype "passive"))
      (node (ref "C4305") (pin "2") (pinfunction "2_2") (pintype "passive"))
      (node (ref "C4306") (pin "2") (pinfunction "2_2") (pintype "passive"))
      (node (ref "C4307") (pin "2") (pinfunction "2_2") (pintype "passive"))
      (node (ref "C4308") (pin "2") (pinfunction "2_2") (pintype "passive"))
      (node (ref "TP_IN_43") (pin "2") (pinfunction "2_2") (pintype "passive"))
      (node (ref "TP_OUT_43") (pin "2") (pinfunction "2_2") (pintype "passive"))
    )
    (net (code "44") (name "GND44") (class "Default")
      (node (ref "C44") (pin "2") (pinfunction "2_2") (pintype "passive"))
      (node (ref "C46") (pin "2") (pinfunction "2_2") (pintype "passive"))
      (node (ref "TP_IN_44") (pin "2") (pinfunction "2_2") (pintype "passive"))
      (node (ref "TP_OUT_44") (pin "2") (pinfunction "2_2") (pintype "passive"))
    )
    (net (code "45") (name "GND45") (class "Default")
      (node (ref "C4501") (pin "2") (pinfunction "2_2") (pintype "passive"))
      (node (ref "C4502") (pin "2") (pinfunction "2_2") (pintype "passive"))
      (node (ref "C4503") (pin "2") (pinfunction "2_2") (pintype "passive"))
      (node (ref "C4504") (pin "2") (pinfunction "2_2") (pintype "passive"))
      (node (ref "C4505") (pin "2") (pinfunction "2_2") (pintype "passive"))
      (node (ref "C4506") (pin "2") (pinfunction "2_2") (pintype "passive"))
      (node (ref "C4507") (pin "2") (pinfunction "2_2") (pintype "passive"))
      (node (ref "C4508") (pin "2") (pinfunction "2_2") (pintype "passive"))
      (node (ref "C4509") (pin "2") (pinfunction "2_2") (pintype "passive"))
      (node (ref "C4510") (pin "2") (pinfunction "2_2") (pintype "passive"))
      (node (ref "TP_IN_45") (pin "2") (pinfunction "2_2") (pintype "passive"))
      (node (ref "TP_OUT_45") (pin "2") (pinfunction "2_2") (pintype "passive"))
    )
    (net (code "46") (name "GND51") (class "Default")
      (node (ref "C51") (pin "2") (pinfunction "2_2") (pintype "passive"))
      (node (ref "TP_IN_51") (pin "2") (pinfunction "2_2") (pintype "passive"))
      (node (ref "TP_OUT_51") (pin "2") (pinfunction "2_2") (pintype "passive"))
    )
    (net (code "47") (name "GND52") (class "Default")
      (node (ref "C5201") (pin "2") (pinfunction "2_2") (pintype "passive"))
      (node (ref "C5202") (pin "2") (pinfunction "2_2") (pintype "passive"))
      (node (ref "C5203") (pin "2") (pinfunction "2_2") (pintype "passive"))
      (node (ref "C5204") (pin "2") (pinfunction "2_2") (pintype "passive"))
      (node (ref "C5205") (pin "2") (pinfunction "2_2") (pintype "passive"))
      (node (ref "C5206") (pin "2") (pinfunction "2_2") (pintype "passive"))
      (node (ref "C5207") (pin "2") (pinfunction "2_2") (pintype "passive"))
      (node (ref "C5208") (pin "2") (pinfunction "2_2") (pintype "passive"))
      (node (ref "TP_IN_52") (pin "2") (pinfunction "2_2") (pintype "passive"))
      (node (ref "TP_OUT_52") (pin "2") (pinfunction "2_2") (pintype "passive"))
    )
    (net (code "48") (name "GND53") (class "Default")
      (node (ref "C5301") (pin "2") (pinfunction "2_2") (pintype "passive"))
      (node (ref "C5302") (pin "2") (pinfunction "2_2") (pintype "passive"))
      (node (ref "C5303") (pin "2") (pinfunction "2_2") (pintype "passive"))
      (node (ref "C5304") (pin "2") (pinfunction "2_2") (pintype "passive"))
      (node (ref "C5305") (pin "2") (pinfunction "2_2") (pintype "passive"))
      (node (ref "C5306") (pin "2") (pinfunction "2_2") (pintype "passive"))
      (node (ref "C5307") (pin "2") (pinfunction "2_2") (pintype "passive"))
      (node (ref "C5308") (pin "2") (pinfunction "2_2") (pintype "passive"))
      (node (ref "TP_IN_53") (pin "2") (pinfunction "2_2") (pintype "passive"))
      (node (ref "TP_OUT_53") (pin "2") (pinfunction "2_2") (pintype "passive"))
    )
    (net (code "49") (name "GND54") (class "Default")
      (node (ref "C54") (pin "2") (pinfunction "2_2") (pintype "passive"))
      (node (ref "TP_IN_54") (pin "2") (pinfunction "2_2") (pintype "passive"))
      (node (ref "TP_OUT_54") (pin "2") (pinfunction "2_2") (pintype "passive"))
    )
    (net (code "50") (name "GND55") (class "Default")
      (node (ref "C55") (pin "2") (pinfunction "2_2") (pintype "passive"))
      (node (ref "TP_IN_55") (pin "2") (pinfunction "2_2") (pintype "passive"))
      (node (ref "TP_OUT_55") (pin "2") (pinfunction "2_2") (pintype "passive"))
    )
  )
)
